# E73-2G4M04S_breakout_sch.net
KiCad netlist of a schematic drawn in Altium Designer
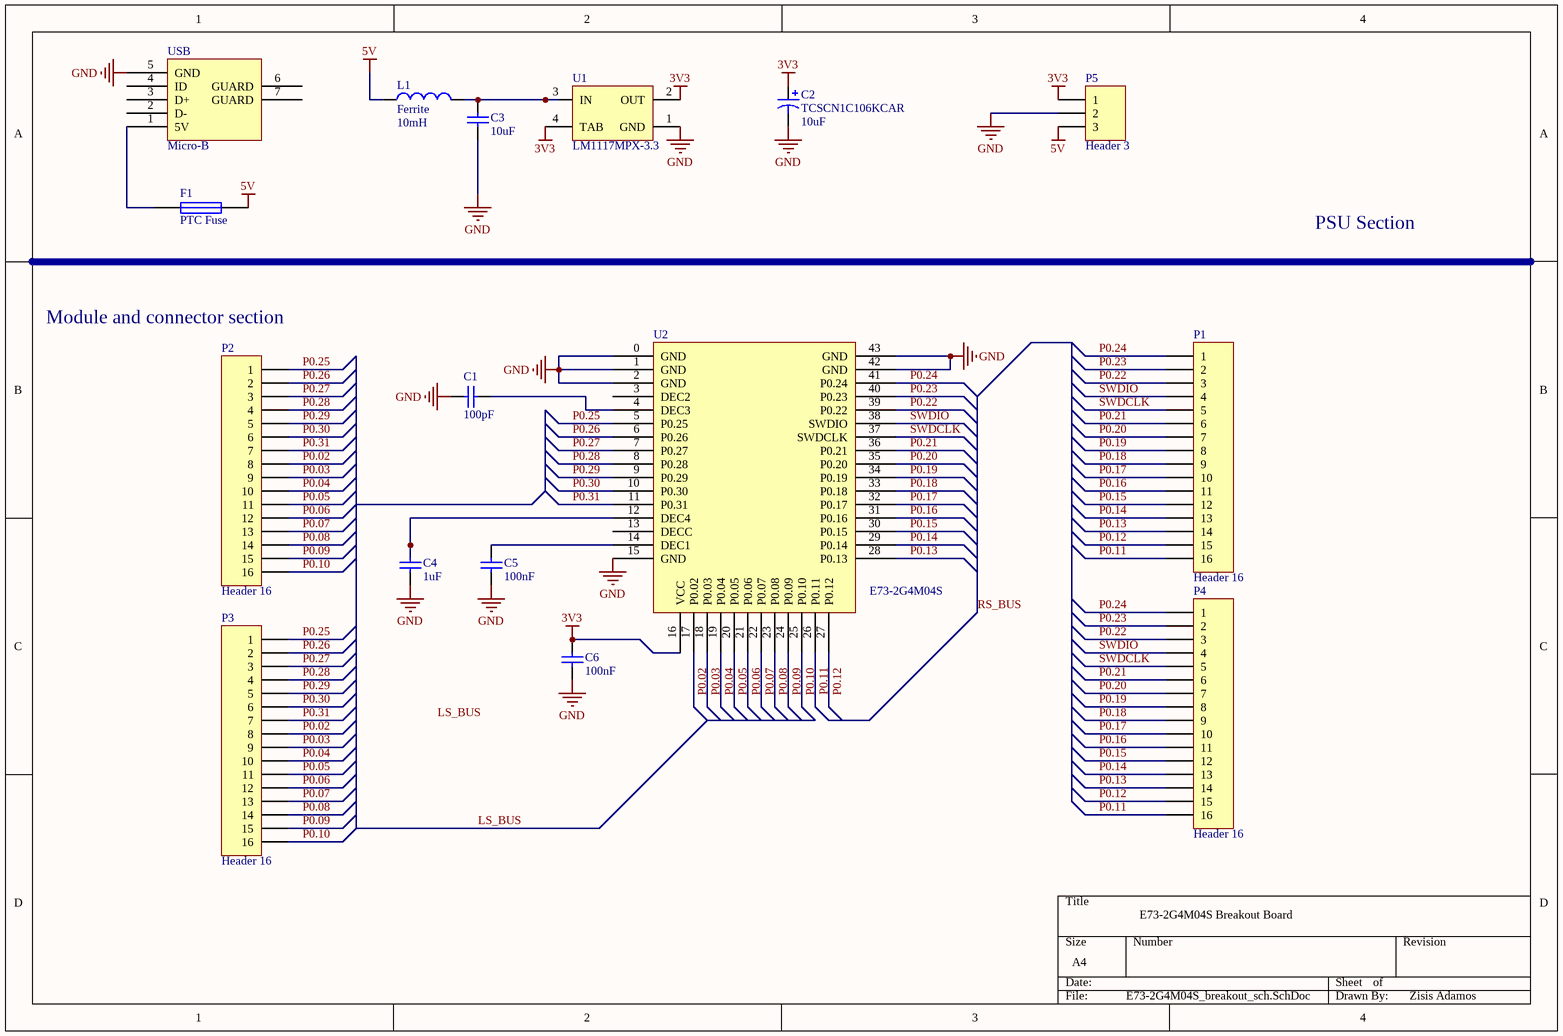
[diagram p0: E73-2G4M04S_breakout_sch.SchDoc]

(export (version "E")
  (design (tool "Eeschema 10.0.6"))
  (components
    (comp (ref "C1")
      (value "100pF")
      (footprint "6-0805_N")
      (description "Capacitor")
      (fields (field (name "Comment") "Cap") (field (name "PUBLISHER") "Altium Limited"))
      (libsource (lib "Miscellaneous Devices") (part "Cap"))
    )
    (comp (ref "C2")
      (value "TCSCN1C106KCAR")
      (footprint "KEMET Chip Capacitor:C")
      (description "Polarized Capacitor (Surface Mount)")
      (fields (field (name "ALTIUM_VALUE") "10uF") (field (name "PUBLISHER") "Altium Limited"))
      (libsource (lib "Miscellaneous Devices") (part "Cap Pol3"))
    )
    (comp (ref "C3")
      (value "10uF")
      (footprint "6-0805_N")
      (description "Capacitor")
      (fields (field (name "Comment") "Cap") (field (name "PUBLISHER") "Altium Limited"))
      (libsource (lib "Miscellaneous Devices") (part "Cap"))
    )
    (comp (ref "C4")
      (value "1uF")
      (footprint "6-0805_N")
      (description "Capacitor")
      (fields (field (name "Comment") "Cap") (field (name "PUBLISHER") "Altium Limited"))
      (libsource (lib "Miscellaneous Devices") (part "Cap"))
    )
    (comp (ref "C5")
      (value "100nF")
      (footprint "6-0805_N")
      (description "Capacitor")
      (fields (field (name "Comment") "Cap") (field (name "PUBLISHER") "Altium Limited"))
      (libsource (lib "Miscellaneous Devices") (part "Cap"))
    )
    (comp (ref "C6")
      (value "100nF")
      (footprint "6-0805_N")
      (description "Capacitor")
      (fields (field (name "Comment") "Cap") (field (name "PUBLISHER") "Altium Limited"))
      (libsource (lib "Miscellaneous Devices") (part "Cap"))
    )
    (comp (ref "F1")
      (value "PTC Fuse")
      (footprint "1210")
      (description "Fuse")
      (fields (field (name "PUBLISHER") "Altium Limited"))
      (libsource (lib "Miscellaneous Devices") (part "Fuse 1"))
    )
    (comp (ref "L1")
      (value "Ferrite")
      (footprint "6-0805_n")
      (description "Inductor")
      (fields (field (name "ALTIUM_VALUE") "10mH") (field (name "PUBLISHER") "Altium Limited"))
      (libsource (lib "Miscellaneous Devices") (part "Inductor"))
    )
    (comp (ref "P1")
      (value "Header 16")
      (footprint "HDR1X16")
      (description "Header, 16-Pin")
      (fields (field (name "PUBLISHER") "Altium Limited"))
      (libsource (lib "") (part "Header 16_1"))
    )
    (comp (ref "P2")
      (value "Header 16")
      (footprint "HDR1X16")
      (description "Header, 16-Pin")
      (fields (field (name "PUBLISHER") "Altium Limited"))
      (libsource (lib "Miscellaneous Connectors") (part "Header 16"))
    )
    (comp (ref "P3")
      (value "Header 16")
      (footprint "HDR1X16")
      (description "Header, 16-Pin")
      (fields (field (name "PUBLISHER") "Altium Limited"))
      (libsource (lib "Miscellaneous Connectors") (part "Header 16"))
    )
    (comp (ref "P4")
      (value "Header 16")
      (footprint "HDR1X16")
      (description "Header, 16-Pin")
      (fields (field (name "PUBLISHER") "Altium Limited"))
      (libsource (lib "") (part "Header 16_1"))
    )
    (comp (ref "P5")
      (value "Header 3")
      (footprint "HDR1X3")
      (description "Header, 3-Pin")
      (fields (field (name "PUBLISHER") "Altium Limited"))
      (libsource (lib "Miscellaneous Connectors") (part "Header 3"))
    )
    (comp (ref "U1")
      (value "LM1117MPX-3.3")
      (footprint "MP04A_N")
      (description "800mA Low-Dropout Linear Regulator, 4-pin SOT-223")
      (fields (field (name "MANUFACTURER") "National Semiconductor"))
      (libsource (lib "National Semiconductor LDO") (part "LM1117MPX-3.3"))
    )
    (comp (ref "U2")
      (value "E73-2G4M04S")
      (footprint "E73-2G4M04S")
      (description "nRF52832 2.4GHz Transceiver Wireless rf Module")
      (libsource (lib "Diafora") (part "E73-2G4M04S"))
    )
    (comp (ref "USB")
      (value "Micro-B")
      (footprint "USB_2_MICRO_B")
      (description "Generic USB Micro-B connector SMT")
      (libsource (lib "Diafora") (part "USB_MICRO_B"))
    )
  )
  (nets
    (net (code "3") (name "/P0.02") (class "Default")
      (node (ref "P2") (pin "8") (pinfunction "8_8") (pintype "passive"))
      (node (ref "P3") (pin "8") (pinfunction "8_8") (pintype "passive"))
      (node (ref "U2") (pin "17") (pinfunction "P0.02_17") (pintype "passive"))
    )
    (net (code "4") (name "/P0.03") (class "Default")
      (node (ref "P2") (pin "9") (pinfunction "9_9") (pintype "passive"))
      (node (ref "P3") (pin "9") (pinfunction "9_9") (pintype "passive"))
      (node (ref "U2") (pin "18") (pinfunction "P0.03_18") (pintype "passive"))
    )
    (net (code "5") (name "/P0.04") (class "Default")
      (node (ref "P2") (pin "10") (pinfunction "10_10") (pintype "passive"))
      (node (ref "P3") (pin "10") (pinfunction "10_10") (pintype "passive"))
      (node (ref "U2") (pin "19") (pinfunction "P0.04_19") (pintype "passive"))
    )
    (net (code "6") (name "/P0.05") (class "Default")
      (node (ref "P2") (pin "11") (pinfunction "11_11") (pintype "passive"))
      (node (ref "P3") (pin "11") (pinfunction "11_11") (pintype "passive"))
      (node (ref "U2") (pin "20") (pinfunction "P0.05_20") (pintype "passive"))
    )
    (net (code "7") (name "/P0.06") (class "Default")
      (node (ref "P2") (pin "12") (pinfunction "12_12") (pintype "passive"))
      (node (ref "P3") (pin "12") (pinfunction "12_12") (pintype "passive"))
      (node (ref "U2") (pin "21") (pinfunction "P0.06_21") (pintype "passive"))
    )
    (net (code "8") (name "/P0.07") (class "Default")
      (node (ref "P2") (pin "13") (pinfunction "13_13") (pintype "passive"))
      (node (ref "P3") (pin "13") (pinfunction "13_13") (pintype "passive"))
      (node (ref "U2") (pin "22") (pinfunction "P0.07_22") (pintype "passive"))
    )
    (net (code "9") (name "/P0.08") (class "Default")
      (node (ref "P2") (pin "14") (pinfunction "14_14") (pintype "passive"))
      (node (ref "P3") (pin "14") (pinfunction "14_14") (pintype "passive"))
      (node (ref "U2") (pin "23") (pinfunction "P0.08_23") (pintype "passive"))
    )
    (net (code "10") (name "/P0.09") (class "Default")
      (node (ref "P2") (pin "15") (pinfunction "15_15") (pintype "passive"))
      (node (ref "P3") (pin "15") (pinfunction "15_15") (pintype "passive"))
      (node (ref "U2") (pin "24") (pinfunction "P0.09_24") (pintype "passive"))
    )
    (net (code "11") (name "/P0.10") (class "Default")
      (node (ref "P2") (pin "16") (pinfunction "16_16") (pintype "passive"))
      (node (ref "P3") (pin "16") (pinfunction "16_16") (pintype "passive"))
      (node (ref "U2") (pin "25") (pinfunction "P0.10_25") (pintype "passive"))
    )
    (net (code "12") (name "/P0.11") (class "Default")
      (node (ref "P1") (pin "16") (pinfunction "16_16") (pintype "passive"))
      (node (ref "P4") (pin "16") (pinfunction "16_16") (pintype "passive"))
      (node (ref "U2") (pin "26") (pinfunction "P0.11_26") (pintype "passive"))
    )
    (net (code "13") (name "/P0.12") (class "Default")
      (node (ref "P1") (pin "15") (pinfunction "15_15") (pintype "passive"))
      (node (ref "P4") (pin "15") (pinfunction "15_15") (pintype "passive"))
      (node (ref "U2") (pin "27") (pinfunction "P0.12_27") (pintype "passive"))
    )
    (net (code "14") (name "/P0.13") (class "Default")
      (node (ref "P1") (pin "14") (pinfunction "14_14") (pintype "passive"))
      (node (ref "P4") (pin "14") (pinfunction "14_14") (pintype "passive"))
      (node (ref "U2") (pin "28") (pinfunction "P0.13_28") (pintype "passive"))
    )
    (net (code "15") (name "/P0.14") (class "Default")
      (node (ref "P1") (pin "13") (pinfunction "13_13") (pintype "passive"))
      (node (ref "P4") (pin "13") (pinfunction "13_13") (pintype "passive"))
      (node (ref "U2") (pin "29") (pinfunction "P0.14_29") (pintype "passive"))
    )
    (net (code "16") (name "/P0.15") (class "Default")
      (node (ref "P1") (pin "12") (pinfunction "12_12") (pintype "passive"))
      (node (ref "P4") (pin "12") (pinfunction "12_12") (pintype "passive"))
      (node (ref "U2") (pin "30") (pinfunction "P0.15_30") (pintype "passive"))
    )
    (net (code "17") (name "/P0.16") (class "Default")
      (node (ref "P1") (pin "11") (pinfunction "11_11") (pintype "passive"))
      (node (ref "P4") (pin "11") (pinfunction "11_11") (pintype "passive"))
      (node (ref "U2") (pin "31") (pinfunction "P0.16_31") (pintype "passive"))
    )
    (net (code "18") (name "/P0.17") (class "Default")
      (node (ref "P1") (pin "10") (pinfunction "10_10") (pintype "passive"))
      (node (ref "P4") (pin "10") (pinfunction "10_10") (pintype "passive"))
      (node (ref "U2") (pin "32") (pinfunction "P0.17_32") (pintype "passive"))
    )
    (net (code "19") (name "/P0.18") (class "Default")
      (node (ref "P1") (pin "9") (pinfunction "9_9") (pintype "passive"))
      (node (ref "P4") (pin "9") (pinfunction "9_9") (pintype "passive"))
      (node (ref "U2") (pin "33") (pinfunction "P0.18_33") (pintype "passive"))
    )
    (net (code "20") (name "/P0.19") (class "Default")
      (node (ref "P1") (pin "8") (pinfunction "8_8") (pintype "passive"))
      (node (ref "P4") (pin "8") (pinfunction "8_8") (pintype "passive"))
      (node (ref "U2") (pin "34") (pinfunction "P0.19_34") (pintype "passive"))
    )
    (net (code "21") (name "/P0.20") (class "Default")
      (node (ref "P1") (pin "7") (pinfunction "7_7") (pintype "passive"))
      (node (ref "P4") (pin "7") (pinfunction "7_7") (pintype "passive"))
      (node (ref "U2") (pin "35") (pinfunction "P0.20_35") (pintype "passive"))
    )
    (net (code "22") (name "/P0.21") (class "Default")
      (node (ref "P1") (pin "6") (pinfunction "6_6") (pintype "passive"))
      (node (ref "P4") (pin "6") (pinfunction "6_6") (pintype "passive"))
      (node (ref "U2") (pin "36") (pinfunction "P0.21_36") (pintype "passive"))
    )
    (net (code "23") (name "/P0.22") (class "Default")
      (node (ref "P1") (pin "3") (pinfunction "3_3") (pintype "passive"))
      (node (ref "P4") (pin "3") (pinfunction "3_3") (pintype "passive"))
      (node (ref "U2") (pin "39") (pinfunction "P0.22_39") (pintype "passive"))
    )
    (net (code "24") (name "/P0.23") (class "Default")
      (node (ref "P1") (pin "2") (pinfunction "2_2") (pintype "passive"))
      (node (ref "P4") (pin "2") (pinfunction "2_2") (pintype "passive"))
      (node (ref "U2") (pin "40") (pinfunction "P0.23_40") (pintype "passive"))
    )
    (net (code "25") (name "/P0.24") (class "Default")
      (node (ref "P1") (pin "1") (pinfunction "1_1") (pintype "passive"))
      (node (ref "P4") (pin "1") (pinfunction "1_1") (pintype "passive"))
      (node (ref "U2") (pin "41") (pinfunction "P0.24_41") (pintype "passive"))
    )
    (net (code "26") (name "/P0.25") (class "Default")
      (node (ref "P2") (pin "1") (pinfunction "1_1") (pintype "passive"))
      (node (ref "P3") (pin "1") (pinfunction "1_1") (pintype "passive"))
      (node (ref "U2") (pin "5") (pinfunction "P0.25_5") (pintype "passive"))
    )
    (net (code "27") (name "/P0.26") (class "Default")
      (node (ref "P2") (pin "2") (pinfunction "2_2") (pintype "passive"))
      (node (ref "P3") (pin "2") (pinfunction "2_2") (pintype "passive"))
      (node (ref "U2") (pin "6") (pinfunction "P0.26_6") (pintype "passive"))
    )
    (net (code "28") (name "/P0.27") (class "Default")
      (node (ref "P2") (pin "3") (pinfunction "3_3") (pintype "passive"))
      (node (ref "P3") (pin "3") (pinfunction "3_3") (pintype "passive"))
      (node (ref "U2") (pin "7") (pinfunction "P0.27_7") (pintype "passive"))
    )
    (net (code "29") (name "/P0.28") (class "Default")
      (node (ref "P2") (pin "4") (pinfunction "4_4") (pintype "passive"))
      (node (ref "P3") (pin "4") (pinfunction "4_4") (pintype "passive"))
      (node (ref "U2") (pin "8") (pinfunction "P0.28_8") (pintype "passive"))
    )
    (net (code "30") (name "/P0.29") (class "Default")
      (node (ref "P2") (pin "5") (pinfunction "5_5") (pintype "passive"))
      (node (ref "P3") (pin "5") (pinfunction "5_5") (pintype "passive"))
      (node (ref "U2") (pin "9") (pinfunction "P0.29_9") (pintype "passive"))
    )
    (net (code "31") (name "/P0.30") (class "Default")
      (node (ref "P2") (pin "6") (pinfunction "6_6") (pintype "passive"))
      (node (ref "P3") (pin "6") (pinfunction "6_6") (pintype "passive"))
      (node (ref "U2") (pin "10") (pinfunction "P0.30_10") (pintype "passive"))
    )
    (net (code "32") (name "/P0.31") (class "Default")
      (node (ref "P2") (pin "7") (pinfunction "7_7") (pintype "passive"))
      (node (ref "P3") (pin "7") (pinfunction "7_7") (pintype "passive"))
      (node (ref "U2") (pin "11") (pinfunction "P0.31_11") (pintype "passive"))
    )
    (net (code "33") (name "/SWDCLK") (class "Default")
      (node (ref "P1") (pin "5") (pinfunction "5_5") (pintype "passive"))
      (node (ref "P4") (pin "5") (pinfunction "5_5") (pintype "passive"))
      (node (ref "U2") (pin "37") (pinfunction "SWDCLK_37") (pintype "passive"))
    )
    (net (code "34") (name "/SWDIO") (class "Default")
      (node (ref "P1") (pin "4") (pinfunction "4_4") (pintype "passive"))
      (node (ref "P4") (pin "4") (pinfunction "4_4") (pintype "passive"))
      (node (ref "U2") (pin "38") (pinfunction "SWDIO_38") (pintype "passive"))
    )
    (net (code "37") (name "3V3") (class "Default")
      (node (ref "C2") (pin "1") (pinfunction "1_1") (pintype "passive"))
      (node (ref "C6") (pin "1") (pinfunction "1_1") (pintype "passive"))
      (node (ref "P5") (pin "1") (pinfunction "1_1") (pintype "passive"))
      (node (ref "U1") (pin "2") (pinfunction "OUT_2") (pintype "power_in"))
      (node (ref "U1") (pin "4") (pinfunction "TAB_4") (pintype "power_in"))
      (node (ref "U2") (pin "16") (pinfunction "VCC_16") (pintype "passive"))
    )
    (net (code "38") (name "5V") (class "Default")
      (node (ref "F1") (pin "2") (pinfunction "2_2") (pintype "passive"))
      (node (ref "L1") (pin "1") (pinfunction "1_1") (pintype "passive"))
      (node (ref "P5") (pin "3") (pinfunction "3_3") (pintype "passive"))
    )
    (net (code "39") (name "GND") (class "Default")
      (node (ref "C1") (pin "1") (pinfunction "1_1") (pintype "passive"))
      (node (ref "C2") (pin "2") (pinfunction "2_2") (pintype "passive"))
      (node (ref "C3") (pin "1") (pinfunction "1_1") (pintype "passive"))
      (node (ref "C4") (pin "2") (pinfunction "2_2") (pintype "passive"))
      (node (ref "C5") (pin "2") (pinfunction "2_2") (pintype "passive"))
      (node (ref "C6") (pin "2") (pinfunction "2_2") (pintype "passive"))
      (node (ref "P5") (pin "2") (pinfunction "2_2") (pintype "passive"))
      (node (ref "U1") (pin "1") (pinfunction "GND_1") (pintype "power_in"))
      (node (ref "U2") (pin "0") (pinfunction "GND_0") (pintype "passive"))
      (node (ref "U2") (pin "1") (pinfunction "GND_1") (pintype "passive"))
      (node (ref "U2") (pin "15") (pinfunction "GND_15") (pintype "passive"))
      (node (ref "U2") (pin "2") (pinfunction "GND_2") (pintype "passive"))
      (node (ref "U2") (pin "42") (pinfunction "GND_42") (pintype "passive"))
      (node (ref "U2") (pin "43") (pinfunction "GND_43") (pintype "passive"))
      (node (ref "USB") (pin "5") (pinfunction "GND_5") (pintype "passive"))
    )
    (net (code "40") (name "Net-(U1-IN)") (class "Default")
      (node (ref "C3") (pin "2") (pinfunction "2_2") (pintype "passive"))
      (node (ref "L1") (pin "2") (pinfunction "2_2") (pintype "passive"))
      (node (ref "U1") (pin "3") (pinfunction "IN_3") (pintype "power_in"))
    )
    (net (code "41") (name "Net-(U2-DEC1)") (class "Default")
      (node (ref "C5") (pin "1") (pinfunction "1_1") (pintype "passive"))
      (node (ref "U2") (pin "14") (pinfunction "DEC1_14") (pintype "passive"))
    )
    (net (code "42") (name "Net-(U2-DEC3)") (class "Default")
      (node (ref "C1") (pin "2") (pinfunction "2_2") (pintype "passive"))
      (node (ref "U2") (pin "4") (pinfunction "DEC3_4") (pintype "passive"))
    )
    (net (code "43") (name "Net-(U2-DEC4)") (class "Default")
      (node (ref "C4") (pin "1") (pinfunction "1_1") (pintype "passive"))
      (node (ref "U2") (pin "12") (pinfunction "DEC4_12") (pintype "passive"))
    )
    (net (code "44") (name "Net-(USB-5V)") (class "Default")
      (node (ref "F1") (pin "1") (pinfunction "1_1") (pintype "passive"))
      (node (ref "USB") (pin "1") (pinfunction "5V_1") (pintype "passive"))
    )
    (net (code "45") (name "unconnected-(U2-DEC2-Pad3)") (class "Default")
      (node (ref "U2") (pin "3") (pinfunction "DEC2_3") (pintype "passive"))
    )
    (net (code "46") (name "unconnected-(U2-DECC-Pad13)") (class "Default")
      (node (ref "U2") (pin "13") (pinfunction "DECC_13") (pintype "passive"))
    )
    (net (code "47") (name "unconnected-(USB-D+-Pad3)") (class "Default")
      (node (ref "USB") (pin "3") (pinfunction "D+_3") (pintype "passive"))
    )
    (net (code "48") (name "unconnected-(USB-D--Pad2)") (class "Default")
      (node (ref "USB") (pin "2") (pinfunction "D-_2") (pintype "passive"))
    )
    (net (code "49") (name "unconnected-(USB-GUARD-Pad6)") (class "Default")
      (node (ref "USB") (pin "6") (pinfunction "GUARD_6") (pintype "passive"))
    )
    (net (code "50") (name "unconnected-(USB-GUARD-Pad7)") (class "Default")
      (node (ref "USB") (pin "7") (pinfunction "GUARD_7") (pintype "passive"))
    )
    (net (code "51") (name "unconnected-(USB-ID-Pad4)") (class "Default")
      (node (ref "USB") (pin "4") (pinfunction "ID_4") (pintype "passive"))
    )
  )
)
